# S203D.net
KiCad netlist of a schematic drawn in EAGLE
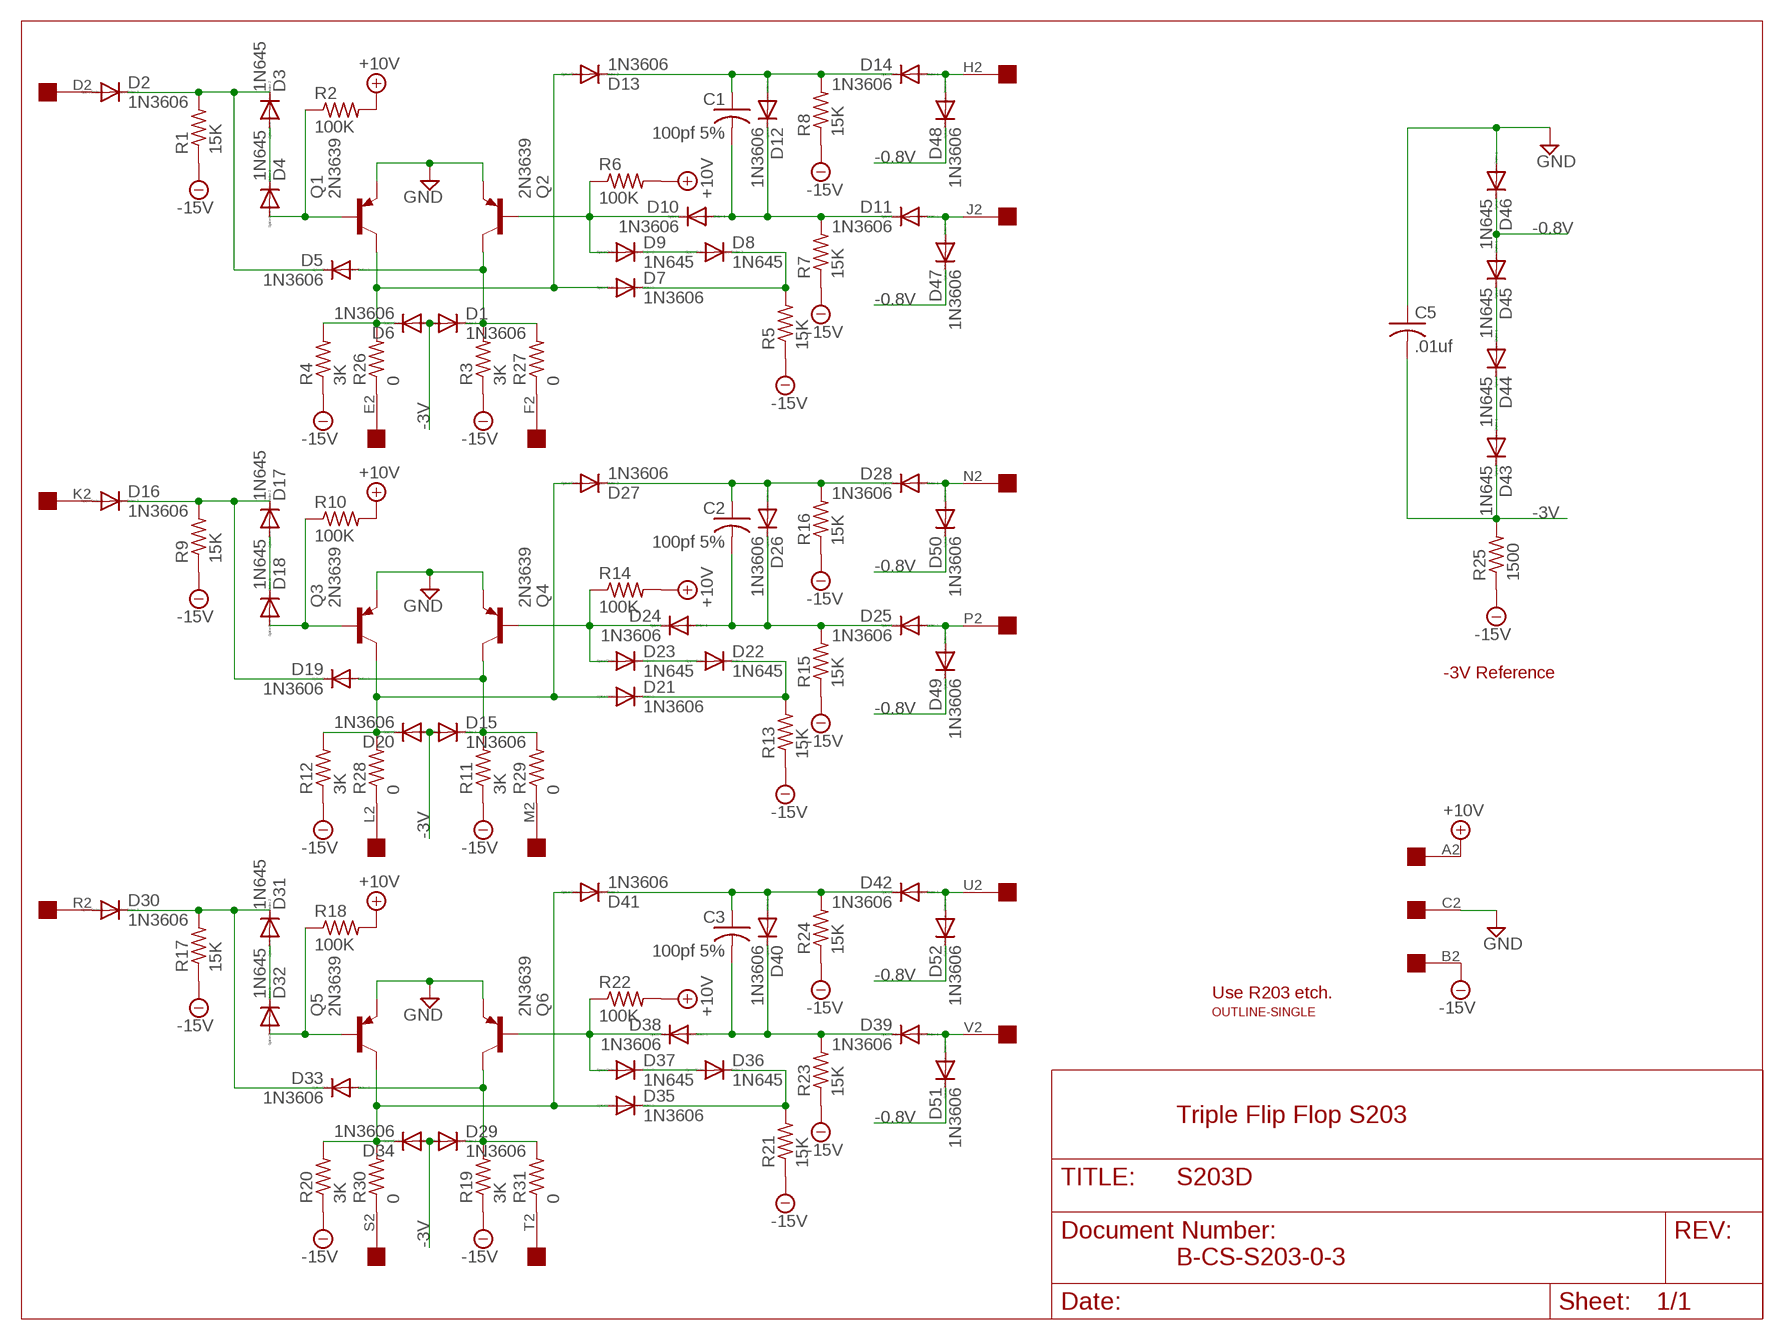
[diagram p0: schematic, sheet 1]

(export (version "E")
  (design (tool "Eeschema 10.0.6"))
  (components
    (comp (ref "C1")
      (value "100pf 5%")
      (footprint "eagle-import:C050-025X075")
      (libsource (lib "eagle-import") (part "C-US050-025X075"))
    )
    (comp (ref "C2")
      (value "100pf 5%")
      (footprint "eagle-import:C050-025X075")
      (libsource (lib "eagle-import") (part "C-US050-025X075"))
    )
    (comp (ref "C3")
      (value "100pf 5%")
      (footprint "eagle-import:C050-025X075")
      (libsource (lib "eagle-import") (part "C-US050-025X075"))
    )
    (comp (ref "C5")
      (value ".01uf")
      (footprint "eagle-import:C050-025X075")
      (libsource (lib "eagle-import") (part "C-US050-025X075"))
    )
    (comp (ref "D1")
      (value "1N3606")
      (footprint "eagle-import:DO35-10")
      (libsource (lib "eagle-import") (part "1N4148DO35-10"))
    )
    (comp (ref "D2")
      (value "1N3606")
      (footprint "eagle-import:DO35-10")
      (libsource (lib "eagle-import") (part "1N4148DO35-10"))
    )
    (comp (ref "D3")
      (value "1N645")
      (footprint "eagle-import:DO35-10")
      (libsource (lib "eagle-import") (part "1N4148DO35-10"))
    )
    (comp (ref "D4")
      (value "1N645")
      (footprint "eagle-import:DO35-10")
      (libsource (lib "eagle-import") (part "1N4148DO35-10"))
    )
    (comp (ref "D5")
      (value "1N3606")
      (footprint "eagle-import:DO35-10")
      (libsource (lib "eagle-import") (part "1N4148DO35-10"))
    )
    (comp (ref "D6")
      (value "1N3606")
      (footprint "eagle-import:DO35-10")
      (libsource (lib "eagle-import") (part "1N4148DO35-10"))
    )
    (comp (ref "D7")
      (value "1N3606")
      (footprint "eagle-import:DO35-10")
      (libsource (lib "eagle-import") (part "1N4148DO35-10"))
    )
    (comp (ref "D8")
      (value "1N645")
      (footprint "eagle-import:DO35-10")
      (libsource (lib "eagle-import") (part "1N4148DO35-10"))
    )
    (comp (ref "D9")
      (value "1N645")
      (footprint "eagle-import:DO35-10")
      (libsource (lib "eagle-import") (part "1N4148DO35-10"))
    )
    (comp (ref "D10")
      (value "1N3606")
      (footprint "eagle-import:DO35-10")
      (libsource (lib "eagle-import") (part "1N4148DO35-10"))
    )
    (comp (ref "D11")
      (value "1N3606")
      (footprint "eagle-import:DO35-10")
      (libsource (lib "eagle-import") (part "1N4148DO35-10"))
    )
    (comp (ref "D12")
      (value "1N3606")
      (footprint "eagle-import:DO35-10")
      (libsource (lib "eagle-import") (part "1N4148DO35-10"))
    )
    (comp (ref "D13")
      (value "1N3606")
      (footprint "eagle-import:DO35-10")
      (libsource (lib "eagle-import") (part "1N4148DO35-10"))
    )
    (comp (ref "D14")
      (value "1N3606")
      (footprint "eagle-import:DO35-10")
      (libsource (lib "eagle-import") (part "1N4148DO35-10"))
    )
    (comp (ref "D15")
      (value "1N3606")
      (footprint "eagle-import:DO35-10")
      (libsource (lib "eagle-import") (part "1N4148DO35-10"))
    )
    (comp (ref "D16")
      (value "1N3606")
      (footprint "eagle-import:DO35-10")
      (libsource (lib "eagle-import") (part "1N4148DO35-10"))
    )
    (comp (ref "D17")
      (value "1N645")
      (footprint "eagle-import:DO35-10")
      (libsource (lib "eagle-import") (part "1N4148DO35-10"))
    )
    (comp (ref "D18")
      (value "1N645")
      (footprint "eagle-import:DO35-10")
      (libsource (lib "eagle-import") (part "1N4148DO35-10"))
    )
    (comp (ref "D19")
      (value "1N3606")
      (footprint "eagle-import:DO35-10")
      (libsource (lib "eagle-import") (part "1N4148DO35-10"))
    )
    (comp (ref "D20")
      (value "1N3606")
      (footprint "eagle-import:DO35-10")
      (libsource (lib "eagle-import") (part "1N4148DO35-10"))
    )
    (comp (ref "D21")
      (value "1N3606")
      (footprint "eagle-import:DO35-10")
      (libsource (lib "eagle-import") (part "1N4148DO35-10"))
    )
    (comp (ref "D22")
      (value "1N645")
      (footprint "eagle-import:DO35-10")
      (libsource (lib "eagle-import") (part "1N4148DO35-10"))
    )
    (comp (ref "D23")
      (value "1N645")
      (footprint "eagle-import:DO35-10")
      (libsource (lib "eagle-import") (part "1N4148DO35-10"))
    )
    (comp (ref "D24")
      (value "1N3606")
      (footprint "eagle-import:DO35-10")
      (libsource (lib "eagle-import") (part "1N4148DO35-10"))
    )
    (comp (ref "D25")
      (value "1N3606")
      (footprint "eagle-import:DO35-10")
      (libsource (lib "eagle-import") (part "1N4148DO35-10"))
    )
    (comp (ref "D26")
      (value "1N3606")
      (footprint "eagle-import:DO35-10")
      (libsource (lib "eagle-import") (part "1N4148DO35-10"))
    )
    (comp (ref "D27")
      (value "1N3606")
      (footprint "eagle-import:DO35-10")
      (libsource (lib "eagle-import") (part "1N4148DO35-10"))
    )
    (comp (ref "D28")
      (value "1N3606")
      (footprint "eagle-import:DO35-10")
      (libsource (lib "eagle-import") (part "1N4148DO35-10"))
    )
    (comp (ref "D29")
      (value "1N3606")
      (footprint "eagle-import:DO35-10")
      (libsource (lib "eagle-import") (part "1N4148DO35-10"))
    )
    (comp (ref "D30")
      (value "1N3606")
      (footprint "eagle-import:DO35-10")
      (libsource (lib "eagle-import") (part "1N4148DO35-10"))
    )
    (comp (ref "D31")
      (value "1N645")
      (footprint "eagle-import:DO35-10")
      (libsource (lib "eagle-import") (part "1N4148DO35-10"))
    )
    (comp (ref "D32")
      (value "1N645")
      (footprint "eagle-import:DO35-10")
      (libsource (lib "eagle-import") (part "1N4148DO35-10"))
    )
    (comp (ref "D33")
      (value "1N3606")
      (footprint "eagle-import:DO35-10")
      (libsource (lib "eagle-import") (part "1N4148DO35-10"))
    )
    (comp (ref "D34")
      (value "1N3606")
      (footprint "eagle-import:DO35-10")
      (libsource (lib "eagle-import") (part "1N4148DO35-10"))
    )
    (comp (ref "D35")
      (value "1N3606")
      (footprint "eagle-import:DO35-10")
      (libsource (lib "eagle-import") (part "1N4148DO35-10"))
    )
    (comp (ref "D36")
      (value "1N645")
      (footprint "eagle-import:DO35-10")
      (libsource (lib "eagle-import") (part "1N4148DO35-10"))
    )
    (comp (ref "D37")
      (value "1N645")
      (footprint "eagle-import:DO35-10")
      (libsource (lib "eagle-import") (part "1N4148DO35-10"))
    )
    (comp (ref "D38")
      (value "1N3606")
      (footprint "eagle-import:DO35-10")
      (libsource (lib "eagle-import") (part "1N4148DO35-10"))
    )
    (comp (ref "D39")
      (value "1N3606")
      (footprint "eagle-import:DO35-10")
      (libsource (lib "eagle-import") (part "1N4148DO35-10"))
    )
    (comp (ref "D40")
      (value "1N3606")
      (footprint "eagle-import:DO35-10")
      (libsource (lib "eagle-import") (part "1N4148DO35-10"))
    )
    (comp (ref "D41")
      (value "1N3606")
      (footprint "eagle-import:DO35-10")
      (libsource (lib "eagle-import") (part "1N4148DO35-10"))
    )
    (comp (ref "D42")
      (value "1N3606")
      (footprint "eagle-import:DO35-10")
      (libsource (lib "eagle-import") (part "1N4148DO35-10"))
    )
    (comp (ref "D43")
      (value "1N645")
      (footprint "eagle-import:DO35-10")
      (libsource (lib "eagle-import") (part "1N4148DO35-10"))
    )
    (comp (ref "D44")
      (value "1N645")
      (footprint "eagle-import:DO35-10")
      (libsource (lib "eagle-import") (part "1N4148DO35-10"))
    )
    (comp (ref "D45")
      (value "1N645")
      (footprint "eagle-import:DO35-10")
      (libsource (lib "eagle-import") (part "1N4148DO35-10"))
    )
    (comp (ref "D46")
      (value "1N645")
      (footprint "eagle-import:DO35-10")
      (libsource (lib "eagle-import") (part "1N4148DO35-10"))
    )
    (comp (ref "D47")
      (value "1N3606")
      (footprint "eagle-import:DO35-10")
      (libsource (lib "eagle-import") (part "1N4148DO35-10"))
    )
    (comp (ref "D48")
      (value "1N3606")
      (footprint "eagle-import:DO35-10")
      (libsource (lib "eagle-import") (part "1N4148DO35-10"))
    )
    (comp (ref "D49")
      (value "1N3606")
      (footprint "eagle-import:DO35-10")
      (libsource (lib "eagle-import") (part "1N4148DO35-10"))
    )
    (comp (ref "D50")
      (value "1N3606")
      (footprint "eagle-import:DO35-10")
      (libsource (lib "eagle-import") (part "1N4148DO35-10"))
    )
    (comp (ref "D51")
      (value "1N3606")
      (footprint "eagle-import:DO35-10")
      (libsource (lib "eagle-import") (part "1N4148DO35-10"))
    )
    (comp (ref "D52")
      (value "1N3606")
      (footprint "eagle-import:DO35-10")
      (libsource (lib "eagle-import") (part "1N4148DO35-10"))
    )
    (comp (ref "Q1")
      (value "2N3639")
      (footprint "eagle-import:TO39")
      (libsource (lib "eagle-import") (part "2N3637"))
    )
    (comp (ref "Q2")
      (value "2N3639")
      (footprint "eagle-import:TO39")
      (libsource (lib "eagle-import") (part "2N3637"))
    )
    (comp (ref "Q3")
      (value "2N3639")
      (footprint "eagle-import:TO39")
      (libsource (lib "eagle-import") (part "2N3637"))
    )
    (comp (ref "Q4")
      (value "2N3639")
      (footprint "eagle-import:TO39")
      (libsource (lib "eagle-import") (part "2N3637"))
    )
    (comp (ref "Q5")
      (value "2N3639")
      (footprint "eagle-import:TO39")
      (libsource (lib "eagle-import") (part "2N3637"))
    )
    (comp (ref "Q6")
      (value "2N3639")
      (footprint "eagle-import:TO39")
      (libsource (lib "eagle-import") (part "2N3637"))
    )
    (comp (ref "R1")
      (value "15K")
      (footprint "eagle-import:0207_10")
      (libsource (lib "eagle-import") (part "R-US_0207/10"))
    )
    (comp (ref "R2")
      (value "100K")
      (footprint "eagle-import:0207_10")
      (libsource (lib "eagle-import") (part "R-US_0207/10"))
    )
    (comp (ref "R3")
      (value "3K")
      (footprint "eagle-import:0207_10")
      (libsource (lib "eagle-import") (part "R-US_0207/10"))
    )
    (comp (ref "R4")
      (value "3K")
      (footprint "eagle-import:0207_10")
      (libsource (lib "eagle-import") (part "R-US_0207/10"))
    )
    (comp (ref "R5")
      (value "15K")
      (footprint "eagle-import:0207_10")
      (libsource (lib "eagle-import") (part "R-US_0207/10"))
    )
    (comp (ref "R6")
      (value "100K")
      (footprint "eagle-import:0207_10")
      (libsource (lib "eagle-import") (part "R-US_0207/10"))
    )
    (comp (ref "R7")
      (value "15K")
      (footprint "eagle-import:0207_10")
      (libsource (lib "eagle-import") (part "R-US_0207/10"))
    )
    (comp (ref "R8")
      (value "15K")
      (footprint "eagle-import:0207_10")
      (libsource (lib "eagle-import") (part "R-US_0207/10"))
    )
    (comp (ref "R9")
      (value "15K")
      (footprint "eagle-import:0207_10")
      (libsource (lib "eagle-import") (part "R-US_0207/10"))
    )
    (comp (ref "R10")
      (value "100K")
      (footprint "eagle-import:0207_10")
      (libsource (lib "eagle-import") (part "R-US_0207/10"))
    )
    (comp (ref "R11")
      (value "3K")
      (footprint "eagle-import:0207_10")
      (libsource (lib "eagle-import") (part "R-US_0207/10"))
    )
    (comp (ref "R12")
      (value "3K")
      (footprint "eagle-import:0207_10")
      (libsource (lib "eagle-import") (part "R-US_0207/10"))
    )
    (comp (ref "R13")
      (value "15K")
      (footprint "eagle-import:0207_10")
      (libsource (lib "eagle-import") (part "R-US_0207/10"))
    )
    (comp (ref "R14")
      (value "100K")
      (footprint "eagle-import:0207_10")
      (libsource (lib "eagle-import") (part "R-US_0207/10"))
    )
    (comp (ref "R15")
      (value "15K")
      (footprint "eagle-import:0207_10")
      (libsource (lib "eagle-import") (part "R-US_0207/10"))
    )
    (comp (ref "R16")
      (value "15K")
      (footprint "eagle-import:0207_10")
      (libsource (lib "eagle-import") (part "R-US_0207/10"))
    )
    (comp (ref "R17")
      (value "15K")
      (footprint "eagle-import:0207_10")
      (libsource (lib "eagle-import") (part "R-US_0207/10"))
    )
    (comp (ref "R18")
      (value "100K")
      (footprint "eagle-import:0207_10")
      (libsource (lib "eagle-import") (part "R-US_0207/10"))
    )
    (comp (ref "R19")
      (value "3K")
      (footprint "eagle-import:0207_10")
      (libsource (lib "eagle-import") (part "R-US_0207/10"))
    )
    (comp (ref "R20")
      (value "3K")
      (footprint "eagle-import:0207_10")
      (libsource (lib "eagle-import") (part "R-US_0207/10"))
    )
    (comp (ref "R21")
      (value "15K")
      (footprint "eagle-import:0207_10")
      (libsource (lib "eagle-import") (part "R-US_0207/10"))
    )
    (comp (ref "R22")
      (value "100K")
      (footprint "eagle-import:0207_10")
      (libsource (lib "eagle-import") (part "R-US_0207/10"))
    )
    (comp (ref "R23")
      (value "15K")
      (footprint "eagle-import:0207_10")
      (libsource (lib "eagle-import") (part "R-US_0207/10"))
    )
    (comp (ref "R24")
      (value "15K")
      (footprint "eagle-import:0207_10")
      (libsource (lib "eagle-import") (part "R-US_0207/10"))
    )
    (comp (ref "R25")
      (value "1500")
      (footprint "eagle-import:0207_10")
      (libsource (lib "eagle-import") (part "R-US_0207/10"))
    )
    (comp (ref "R26")
      (value "0")
      (footprint "eagle-import:0207_10")
      (libsource (lib "eagle-import") (part "R-US_0207/10"))
    )
    (comp (ref "R27")
      (value "0")
      (footprint "eagle-import:0207_10")
      (libsource (lib "eagle-import") (part "R-US_0207/10"))
    )
    (comp (ref "R28")
      (value "0")
      (footprint "eagle-import:0207_10")
      (libsource (lib "eagle-import") (part "R-US_0207/10"))
    )
    (comp (ref "R29")
      (value "0")
      (footprint "eagle-import:0207_10")
      (libsource (lib "eagle-import") (part "R-US_0207/10"))
    )
    (comp (ref "R30")
      (value "0")
      (footprint "eagle-import:0207_10")
      (libsource (lib "eagle-import") (part "R-US_0207/10"))
    )
    (comp (ref "R31")
      (value "0")
      (footprint "eagle-import:0207_10")
      (libsource (lib "eagle-import") (part "R-US_0207/10"))
    )
    (comp (ref "U$1")
      (value "OUTLINE-SINGLE")
      (footprint "eagle-import:SINGLE")
      (libsource (lib "eagle-import") (part "OUTLINE-SINGLE"))
    )
    (comp (ref "U$2")
      (value "EDGE-1")
      (footprint "eagle-import:EDGE-CON1")
      (libsource (lib "eagle-import") (part "EDGE-1"))
    )
  )
  (nets
    (net (code "1") (name "+10V") (class "Default")
      (node (ref "R10") (pin "2") (pinfunction "2_2") (pintype "passive"))
      (node (ref "R14") (pin "2") (pinfunction "2_2") (pintype "passive"))
      (node (ref "R18") (pin "2") (pinfunction "2_2") (pintype "passive"))
      (node (ref "R2") (pin "2") (pinfunction "2_2") (pintype "passive"))
      (node (ref "R22") (pin "2") (pinfunction "2_2") (pintype "passive"))
      (node (ref "R6") (pin "2") (pinfunction "2_2") (pintype "passive"))
      (node (ref "U$2") (pin "A2") (pinfunction "1_A2") (pintype "bidirectional"))
    )
    (net (code "2") (name "-15V") (class "Default")
      (node (ref "R1") (pin "1") (pinfunction "1_1") (pintype "passive"))
      (node (ref "R11") (pin "1") (pinfunction "1_1") (pintype "passive"))
      (node (ref "R12") (pin "1") (pinfunction "1_1") (pintype "passive"))
      (node (ref "R13") (pin "1") (pinfunction "1_1") (pintype "passive"))
      (node (ref "R15") (pin "1") (pinfunction "1_1") (pintype "passive"))
      (node (ref "R16") (pin "1") (pinfunction "1_1") (pintype "passive"))
      (node (ref "R17") (pin "1") (pinfunction "1_1") (pintype "passive"))
      (node (ref "R19") (pin "1") (pinfunction "1_1") (pintype "passive"))
      (node (ref "R20") (pin "1") (pinfunction "1_1") (pintype "passive"))
      (node (ref "R21") (pin "1") (pinfunction "1_1") (pintype "passive"))
      (node (ref "R23") (pin "1") (pinfunction "1_1") (pintype "passive"))
      (node (ref "R24") (pin "1") (pinfunction "1_1") (pintype "passive"))
      (node (ref "R25") (pin "1") (pinfunction "1_1") (pintype "passive"))
      (node (ref "R3") (pin "1") (pinfunction "1_1") (pintype "passive"))
      (node (ref "R4") (pin "1") (pinfunction "1_1") (pintype "passive"))
      (node (ref "R5") (pin "1") (pinfunction "1_1") (pintype "passive"))
      (node (ref "R7") (pin "1") (pinfunction "1_1") (pintype "passive"))
      (node (ref "R8") (pin "1") (pinfunction "1_1") (pintype "passive"))
      (node (ref "R9") (pin "1") (pinfunction "1_1") (pintype "passive"))
      (node (ref "U$2") (pin "B2") (pinfunction "1_B2") (pintype "bidirectional"))
    )
    (net (code "3") (name "/-0.8V") (class "Default")
      (node (ref "D45") (pin "A") (pinfunction "A_A") (pintype "passive"))
      (node (ref "D46") (pin "C") (pinfunction "C_C") (pintype "passive"))
      (node (ref "D47") (pin "C") (pinfunction "C_C") (pintype "passive"))
      (node (ref "D48") (pin "C") (pinfunction "C_C") (pintype "passive"))
      (node (ref "D49") (pin "C") (pinfunction "C_C") (pintype "passive"))
      (node (ref "D50") (pin "C") (pinfunction "C_C") (pintype "passive"))
      (node (ref "D51") (pin "C") (pinfunction "C_C") (pintype "passive"))
      (node (ref "D52") (pin "C") (pinfunction "C_C") (pintype "passive"))
    )
    (net (code "4") (name "/-3V") (class "Default")
      (node (ref "C5") (pin "2") (pinfunction "2_2") (pintype "passive"))
      (node (ref "D1") (pin "A") (pinfunction "A_A") (pintype "passive"))
      (node (ref "D15") (pin "A") (pinfunction "A_A") (pintype "passive"))
      (node (ref "D20") (pin "A") (pinfunction "A_A") (pintype "passive"))
      (node (ref "D29") (pin "A") (pinfunction "A_A") (pintype "passive"))
      (node (ref "D34") (pin "A") (pinfunction "A_A") (pintype "passive"))
      (node (ref "D43") (pin "C") (pinfunction "C_C") (pintype "passive"))
      (node (ref "D6") (pin "A") (pinfunction "A_A") (pintype "passive"))
      (node (ref "R25") (pin "2") (pinfunction "2_2") (pintype "passive"))
    )
    (net (code "5") (name "GND") (class "Default")
      (node (ref "C5") (pin "1") (pinfunction "1_1") (pintype "passive"))
      (node (ref "D46") (pin "A") (pinfunction "A_A") (pintype "passive"))
      (node (ref "Q1") (pin "1") (pinfunction "E_1") (pintype "passive"))
      (node (ref "Q2") (pin "1") (pinfunction "E_1") (pintype "passive"))
      (node (ref "Q3") (pin "1") (pinfunction "E_1") (pintype "passive"))
      (node (ref "Q4") (pin "1") (pinfunction "E_1") (pintype "passive"))
      (node (ref "Q5") (pin "1") (pinfunction "E_1") (pintype "passive"))
      (node (ref "Q6") (pin "1") (pinfunction "E_1") (pintype "passive"))
      (node (ref "U$2") (pin "C2") (pinfunction "1_C2") (pintype "bidirectional"))
    )
    (net (code "6") (name "Net-(C1-Pad1)") (class "Default")
      (node (ref "C1") (pin "1") (pinfunction "1_1") (pintype "passive"))
      (node (ref "D12") (pin "A") (pinfunction "A_A") (pintype "passive"))
      (node (ref "D13") (pin "C") (pinfunction "C_C") (pintype "passive"))
      (node (ref "D14") (pin "C") (pinfunction "C_C") (pintype "passive"))
      (node (ref "R8") (pin "2") (pinfunction "2_2") (pintype "passive"))
    )
    (net (code "7") (name "Net-(C1-Pad2)") (class "Default")
      (node (ref "C1") (pin "2") (pinfunction "2_2") (pintype "passive"))
      (node (ref "D10") (pin "A") (pinfunction "A_A") (pintype "passive"))
      (node (ref "D11") (pin "C") (pinfunction "C_C") (pintype "passive"))
      (node (ref "D12") (pin "C") (pinfunction "C_C") (pintype "passive"))
      (node (ref "R7") (pin "2") (pinfunction "2_2") (pintype "passive"))
    )
    (net (code "8") (name "Net-(C2-Pad1)") (class "Default")
      (node (ref "C2") (pin "1") (pinfunction "1_1") (pintype "passive"))
      (node (ref "D26") (pin "A") (pinfunction "A_A") (pintype "passive"))
      (node (ref "D27") (pin "C") (pinfunction "C_C") (pintype "passive"))
      (node (ref "D28") (pin "C") (pinfunction "C_C") (pintype "passive"))
      (node (ref "R16") (pin "2") (pinfunction "2_2") (pintype "passive"))
    )
    (net (code "9") (name "Net-(C2-Pad2)") (class "Default")
      (node (ref "C2") (pin "2") (pinfunction "2_2") (pintype "passive"))
      (node (ref "D24") (pin "A") (pinfunction "A_A") (pintype "passive"))
      (node (ref "D25") (pin "C") (pinfunction "C_C") (pintype "passive"))
      (node (ref "D26") (pin "C") (pinfunction "C_C") (pintype "passive"))
      (node (ref "R15") (pin "2") (pinfunction "2_2") (pintype "passive"))
    )
    (net (code "10") (name "Net-(C3-Pad1)") (class "Default")
      (node (ref "C3") (pin "1") (pinfunction "1_1") (pintype "passive"))
      (node (ref "D40") (pin "A") (pinfunction "A_A") (pintype "passive"))
      (node (ref "D41") (pin "C") (pinfunction "C_C") (pintype "passive"))
      (node (ref "D42") (pin "C") (pinfunction "C_C") (pintype "passive"))
      (node (ref "R24") (pin "2") (pinfunction "2_2") (pintype "passive"))
    )
    (net (code "11") (name "Net-(C3-Pad2)") (class "Default")
      (node (ref "C3") (pin "2") (pinfunction "2_2") (pintype "passive"))
      (node (ref "D38") (pin "A") (pinfunction "A_A") (pintype "passive"))
      (node (ref "D39") (pin "C") (pinfunction "C_C") (pintype "passive"))
      (node (ref "D40") (pin "C") (pinfunction "C_C") (pintype "passive"))
      (node (ref "R23") (pin "2") (pinfunction "2_2") (pintype "passive"))
    )
    (net (code "12") (name "Net-(D2-PadC)") (class "Default")
      (node (ref "D2") (pin "C") (pinfunction "C_C") (pintype "passive"))
      (node (ref "D3") (pin "C") (pinfunction "C_C") (pintype "passive"))
      (node (ref "D5") (pin "C") (pinfunction "C_C") (pintype "passive"))
      (node (ref "R1") (pin "2") (pinfunction "2_2") (pintype "passive"))
    )
    (net (code "13") (name "Net-(D3-PadA)") (class "Default")
      (node (ref "D3") (pin "A") (pinfunction "A_A") (pintype "passive"))
      (node (ref "D4") (pin "C") (pinfunction "C_C") (pintype "passive"))
    )
    (net (code "14") (name "Net-(D7-PadC)") (class "Default")
      (node (ref "D7") (pin "C") (pinfunction "C_C") (pintype "passive"))
      (node (ref "D8") (pin "C") (pinfunction "C_C") (pintype "passive"))
      (node (ref "R5") (pin "2") (pinfunction "2_2") (pintype "passive"))
    )
    (net (code "15") (name "Net-(D8-PadA)") (class "Default")
      (node (ref "D8") (pin "A") (pinfunction "A_A") (pintype "passive"))
      (node (ref "D9") (pin "C") (pinfunction "C_C") (pintype "passive"))
    )
    (net (code "16") (name "Net-(D16-PadC)") (class "Default")
      (node (ref "D16") (pin "C") (pinfunction "C_C") (pintype "passive"))
      (node (ref "D17") (pin "C") (pinfunction "C_C") (pintype "passive"))
      (node (ref "D19") (pin "C") (pinfunction "C_C") (pintype "passive"))
      (node (ref "R9") (pin "2") (pinfunction "2_2") (pintype "passive"))
    )
    (net (code "17") (name "Net-(D17-PadA)") (class "Default")
      (node (ref "D17") (pin "A") (pinfunction "A_A") (pintype "passive"))
      (node (ref "D18") (pin "C") (pinfunction "C_C") (pintype "passive"))
    )
    (net (code "18") (name "Net-(D21-PadC)") (class "Default")
      (node (ref "D21") (pin "C") (pinfunction "C_C") (pintype "passive"))
      (node (ref "D22") (pin "C") (pinfunction "C_C") (pintype "passive"))
      (node (ref "R13") (pin "2") (pinfunction "2_2") (pintype "passive"))
    )
    (net (code "19") (name "Net-(D22-PadA)") (class "Default")
      (node (ref "D22") (pin "A") (pinfunction "A_A") (pintype "passive"))
      (node (ref "D23") (pin "C") (pinfunction "C_C") (pintype "passive"))
    )
    (net (code "20") (name "Net-(D30-PadC)") (class "Default")
      (node (ref "D30") (pin "C") (pinfunction "C_C") (pintype "passive"))
      (node (ref "D31") (pin "C") (pinfunction "C_C") (pintype "passive"))
      (node (ref "D33") (pin "C") (pinfunction "C_C") (pintype "passive"))
      (node (ref "R17") (pin "2") (pinfunction "2_2") (pintype "passive"))
    )
    (net (code "21") (name "Net-(D31-PadA)") (class "Default")
      (node (ref "D31") (pin "A") (pinfunction "A_A") (pintype "passive"))
      (node (ref "D32") (pin "C") (pinfunction "C_C") (pintype "passive"))
    )
    (net (code "22") (name "Net-(D35-PadC)") (class "Default")
      (node (ref "D35") (pin "C") (pinfunction "C_C") (pintype "passive"))
      (node (ref "D36") (pin "C") (pinfunction "C_C") (pintype "passive"))
      (node (ref "R21") (pin "2") (pinfunction "2_2") (pintype "passive"))
    )
    (net (code "23") (name "Net-(D36-PadA)") (class "Default")
      (node (ref "D36") (pin "A") (pinfunction "A_A") (pintype "passive"))
      (node (ref "D37") (pin "C") (pinfunction "C_C") (pintype "passive"))
    )
    (net (code "24") (name "Net-(D43-PadA)") (class "Default")
      (node (ref "D43") (pin "A") (pinfunction "A_A") (pintype "passive"))
      (node (ref "D44") (pin "C") (pinfunction "C_C") (pintype "passive"))
    )
    (net (code "25") (name "Net-(D44-PadA)") (class "Default")
      (node (ref "D44") (pin "A") (pinfunction "A_A") (pintype "passive"))
      (node (ref "D45") (pin "C") (pinfunction "C_C") (pintype "passive"))
    )
    (net (code "26") (name "Net-(Q1-B)") (class "Default")
      (node (ref "D4") (pin "A") (pinfunction "A_A") (pintype "passive"))
      (node (ref "Q1") (pin "2") (pinfunction "B_2") (pintype "passive"))
      (node (ref "R2") (pin "1") (pinfunction "1_1") (pintype "passive"))
    )
    (net (code "27") (name "Net-(Q1-C)") (class "Default")
      (node (ref "D13") (pin "A") (pinfunction "A_A") (pintype "passive"))
      (node (ref "D6") (pin "C") (pinfunction "C_C") (pintype "passive"))
      (node (ref "D7") (pin "A") (pinfunction "A_A") (pintype "passive"))
      (node (ref "Q1") (pin "3") (pinfunction "C_3") (pintype "passive"))
      (node (ref "R26") (pin "2") (pinfunction "2_2") (pintype "passive"))
      (node (ref "R4") (pin "2") (pinfunction "2_2") (pintype "passive"))
    )
    (net (code "28") (name "Net-(Q2-B)") (class "Default")
      (node (ref "D10") (pin "C") (pinfunction "C_C") (pintype "passive"))
      (node (ref "D9") (pin "A") (pinfunction "A_A") (pintype "passive"))
      (node (ref "Q2") (pin "2") (pinfunction "B_2") (pintype "passive"))
      (node (ref "R6") (pin "1") (pinfunction "1_1") (pintype "passive"))
    )
    (net (code "29") (name "Net-(Q2-C)") (class "Default")
      (node (ref "D1") (pin "C") (pinfunction "C_C") (pintype "passive"))
      (node (ref "D5") (pin "A") (pinfunction "A_A") (pintype "passive"))
      (node (ref "Q2") (pin "3") (pinfunction "C_3") (pintype "passive"))
      (node (ref "R27") (pin "2") (pinfunction "2_2") (pintype "passive"))
      (node (ref "R3") (pin "2") (pinfunction "2_2") (pintype "passive"))
    )
    (net (code "30") (name "Net-(Q3-B)") (class "Default")
      (node (ref "D18") (pin "A") (pinfunction "A_A") (pintype "passive"))
      (node (ref "Q3") (pin "2") (pinfunction "B_2") (pintype "passive"))
      (node (ref "R10") (pin "1") (pinfunction "1_1") (pintype "passive"))
    )
    (net (code "31") (name "Net-(Q3-C)") (class "Default")
      (node (ref "D20") (pin "C") (pinfunction "C_C") (pintype "passive"))
      (node (ref "D21") (pin "A") (pinfunction "A_A") (pintype "passive"))
      (node (ref "D27") (pin "A") (pinfunction "A_A") (pintype "passive"))
      (node (ref "Q3") (pin "3") (pinfunction "C_3") (pintype "passive"))
      (node (ref "R12") (pin "2") (pinfunction "2_2") (pintype "passive"))
      (node (ref "R28") (pin "2") (pinfunction "2_2") (pintype "passive"))
    )
    (net (code "32") (name "Net-(Q4-B)") (class "Default")
      (node (ref "D23") (pin "A") (pinfunction "A_A") (pintype "passive"))
      (node (ref "D24") (pin "C") (pinfunction "C_C") (pintype "passive"))
      (node (ref "Q4") (pin "2") (pinfunction "B_2") (pintype "passive"))
      (node (ref "R14") (pin "1") (pinfunction "1_1") (pintype "passive"))
    )
    (net (code "33") (name "Net-(Q4-C)") (class "Default")
      (node (ref "D15") (pin "C") (pinfunction "C_C") (pintype "passive"))
      (node (ref "D19") (pin "A") (pinfunction "A_A") (pintype "passive"))
      (node (ref "Q4") (pin "3") (pinfunction "C_3") (pintype "passive"))
      (node (ref "R11") (pin "2") (pinfunction "2_2") (pintype "passive"))
      (node (ref "R29") (pin "2") (pinfunction "2_2") (pintype "passive"))
    )
    (net (code "34") (name "Net-(Q5-B)") (class "Default")
      (node (ref "D32") (pin "A") (pinfunction "A_A") (pintype "passive"))
      (node (ref "Q5") (pin "2") (pinfunction "B_2") (pintype "passive"))
      (node (ref "R18") (pin "1") (pinfunction "1_1") (pintype "passive"))
    )
    (net (code "35") (name "Net-(Q5-C)") (class "Default")
      (node (ref "D34") (pin "C") (pinfunction "C_C") (pintype "passive"))
      (node (ref "D35") (pin "A") (pinfunction "A_A") (pintype "passive"))
      (node (ref "D41") (pin "A") (pinfunction "A_A") (pintype "passive"))
      (node (ref "Q5") (pin "3") (pinfunction "C_3") (pintype "passive"))
      (node (ref "R20") (pin "2") (pinfunction "2_2") (pintype "passive"))
      (node (ref "R30") (pin "2") (pinfunction "2_2") (pintype "passive"))
    )
    (net (code "36") (name "Net-(Q6-B)") (class "Default")
      (node (ref "D37") (pin "A") (pinfunction "A_A") (pintype "passive"))
      (node (ref "D38") (pin "C") (pinfunction "C_C") (pintype "passive"))
      (node (ref "Q6") (pin "2") (pinfunction "B_2") (pintype "passive"))
      (node (ref "R22") (pin "1") (pinfunction "1_1") (pintype "passive"))
    )
    (net (code "37") (name "Net-(Q6-C)") (class "Default")
      (node (ref "D29") (pin "C") (pinfunction "C_C") (pintype "passive"))
      (node (ref "D33") (pin "A") (pinfunction "A_A") (pintype "passive"))
      (node (ref "Q6") (pin "3") (pinfunction "C_3") (pintype "passive"))
      (node (ref "R19") (pin "2") (pinfunction "2_2") (pintype "passive"))
      (node (ref "R31") (pin "2") (pinfunction "2_2") (pintype "passive"))
    )
    (net (code "38") (name "Net-(U$2D-1)") (class "Default")
      (node (ref "D2") (pin "A") (pinfunction "A_A") (pintype "passive"))
      (node (ref "U$2") (pin "D2") (pinfunction "1_D2") (pintype "bidirectional"))
    )
    (net (code "39") (name "Net-(U$2E-1)") (class "Default")
      (node (ref "R26") (pin "1") (pinfunction "1_1") (pintype "passive"))
      (node (ref "U$2") (pin "E2") (pinfunction "1_E2") (pintype "bidirectional"))
    )
    (net (code "40") (name "Net-(U$2F-1)") (class "Default")
      (node (ref "R27") (pin "1") (pinfunction "1_1") (pintype "passive"))
      (node (ref "U$2") (pin "F2") (pinfunction "1_F2") (pintype "bidirectional"))
    )
    (net (code "41") (name "Net-(U$2G-1)") (class "Default")
      (node (ref "D14") (pin "A") (pinfunction "A_A") (pintype "passive"))
      (node (ref "D48") (pin "A") (pinfunction "A_A") (pintype "passive"))
      (node (ref "U$2") (pin "H2") (pinfunction "1_H2") (pintype "bidirectional"))
    )
    (net (code "42") (name "Net-(U$2H-1)") (class "Default")
      (node (ref "D11") (pin "A") (pinfunction "A_A") (pintype "passive"))
      (node (ref "D47") (pin "A") (pinfunction "A_A") (pintype "passive"))
      (node (ref "U$2") (pin "J2") (pinfunction "1_J2") (pintype "bidirectional"))
    )
    (net (code "43") (name "Net-(U$2I-1)") (class "Default")
      (node (ref "D16") (pin "A") (pinfunction "A_A") (pintype "passive"))
      (node (ref "U$2") (pin "K2") (pinfunction "1_K2") (pintype "bidirectional"))
    )
    (net (code "44") (name "Net-(U$2J-1)") (class "Default")
      (node (ref "R28") (pin "1") (pinfunction "1_1") (pintype "passive"))
      (node (ref "U$2") (pin "L2") (pinfunction "1_L2") (pintype "bidirectional"))
    )
    (net (code "45") (name "Net-(U$2K-1)") (class "Default")
      (node (ref "R29") (pin "1") (pinfunction "1_1") (pintype "passive"))
      (node (ref "U$2") (pin "M2") (pinfunction "1_M2") (pintype "bidirectional"))
    )
    (net (code "46") (name "Net-(U$2L-1)") (class "Default")
      (node (ref "D28") (pin "A") (pinfunction "A_A") (pintype "passive"))
      (node (ref "D50") (pin "A") (pinfunction "A_A") (pintype "passive"))
      (node (ref "U$2") (pin "N2") (pinfunction "1_N2") (pintype "bidirectional"))
    )
    (net (code "47") (name "Net-(U$2M-1)") (class "Default")
      (node (ref "D25") (pin "A") (pinfunction "A_A") (pintype "passive"))
      (node (ref "D49") (pin "A") (pinfunction "A_A") (pintype "passive"))
      (node (ref "U$2") (pin "P2") (pinfunction "1_P2") (pintype "bidirectional"))
    )
    (net (code "48") (name "Net-(U$2N-1)") (class "Default")
      (node (ref "D30") (pin "A") (pinfunction "A_A") (pintype "passive"))
      (node (ref "U$2") (pin "R2") (pinfunction "1_R2") (pintype "bidirectional"))
    )
    (net (code "49") (name "Net-(U$2O-1)") (class "Default")
      (node (ref "R30") (pin "1") (pinfunction "1_1") (pintype "passive"))
      (node (ref "U$2") (pin "S2") (pinfunction "1_S2") (pintype "bidirectional"))
    )
    (net (code "50") (name "Net-(U$2P-1)") (class "Default")
      (node (ref "R31") (pin "1") (pinfunction "1_1") (pintype "passive"))
      (node (ref "U$2") (pin "T2") (pinfunction "1_T2") (pintype "bidirectional"))
    )
    (net (code "51") (name "Net-(U$2Q-1)") (class "Default")
      (node (ref "D42") (pin "A") (pinfunction "A_A") (pintype "passive"))
      (node (ref "D52") (pin "A") (pinfunction "A_A") (pintype "passive"))
      (node (ref "U$2") (pin "U2") (pinfunction "1_U2") (pintype "bidirectional"))
    )
    (net (code "52") (name "Net-(U$2R-1)") (class "Default")
      (node (ref "D39") (pin "A") (pinfunction "A_A") (pintype "passive"))
      (node (ref "D51") (pin "A") (pinfunction "A_A") (pintype "passive"))
      (node (ref "U$2") (pin "V2") (pinfunction "1_V2") (pintype "bidirectional"))
    )
  )
)
